# eps_flatsat_module.net
KiCad netlist of a schematic drawn in EAGLE
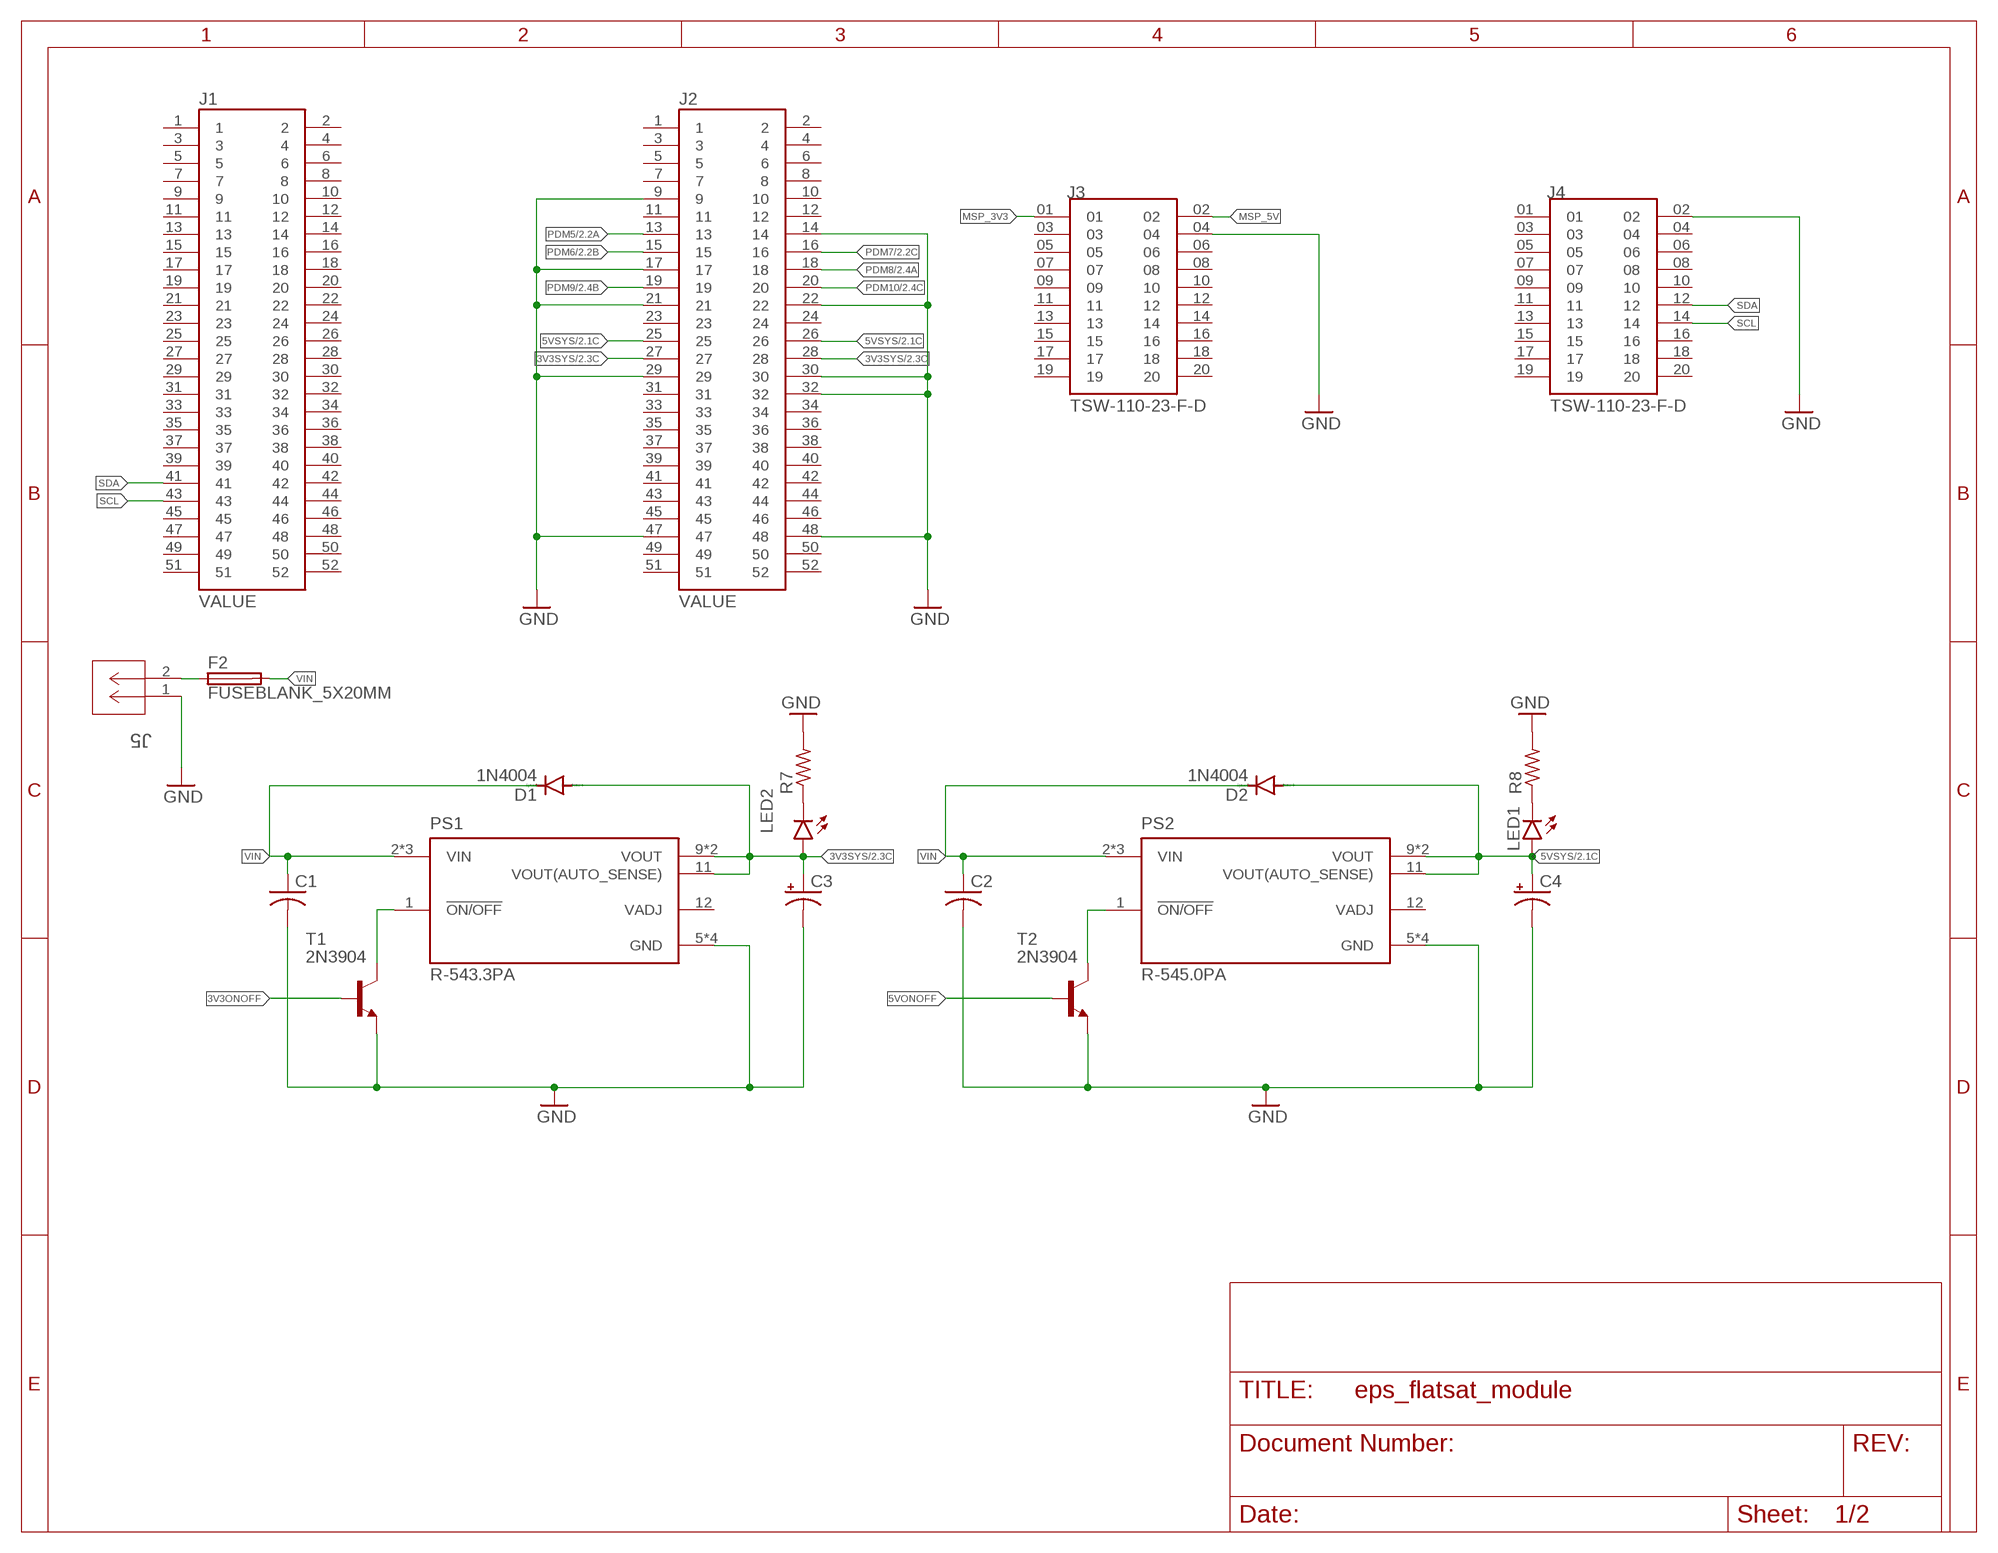
[diagram p0: schematic, sheet 1]
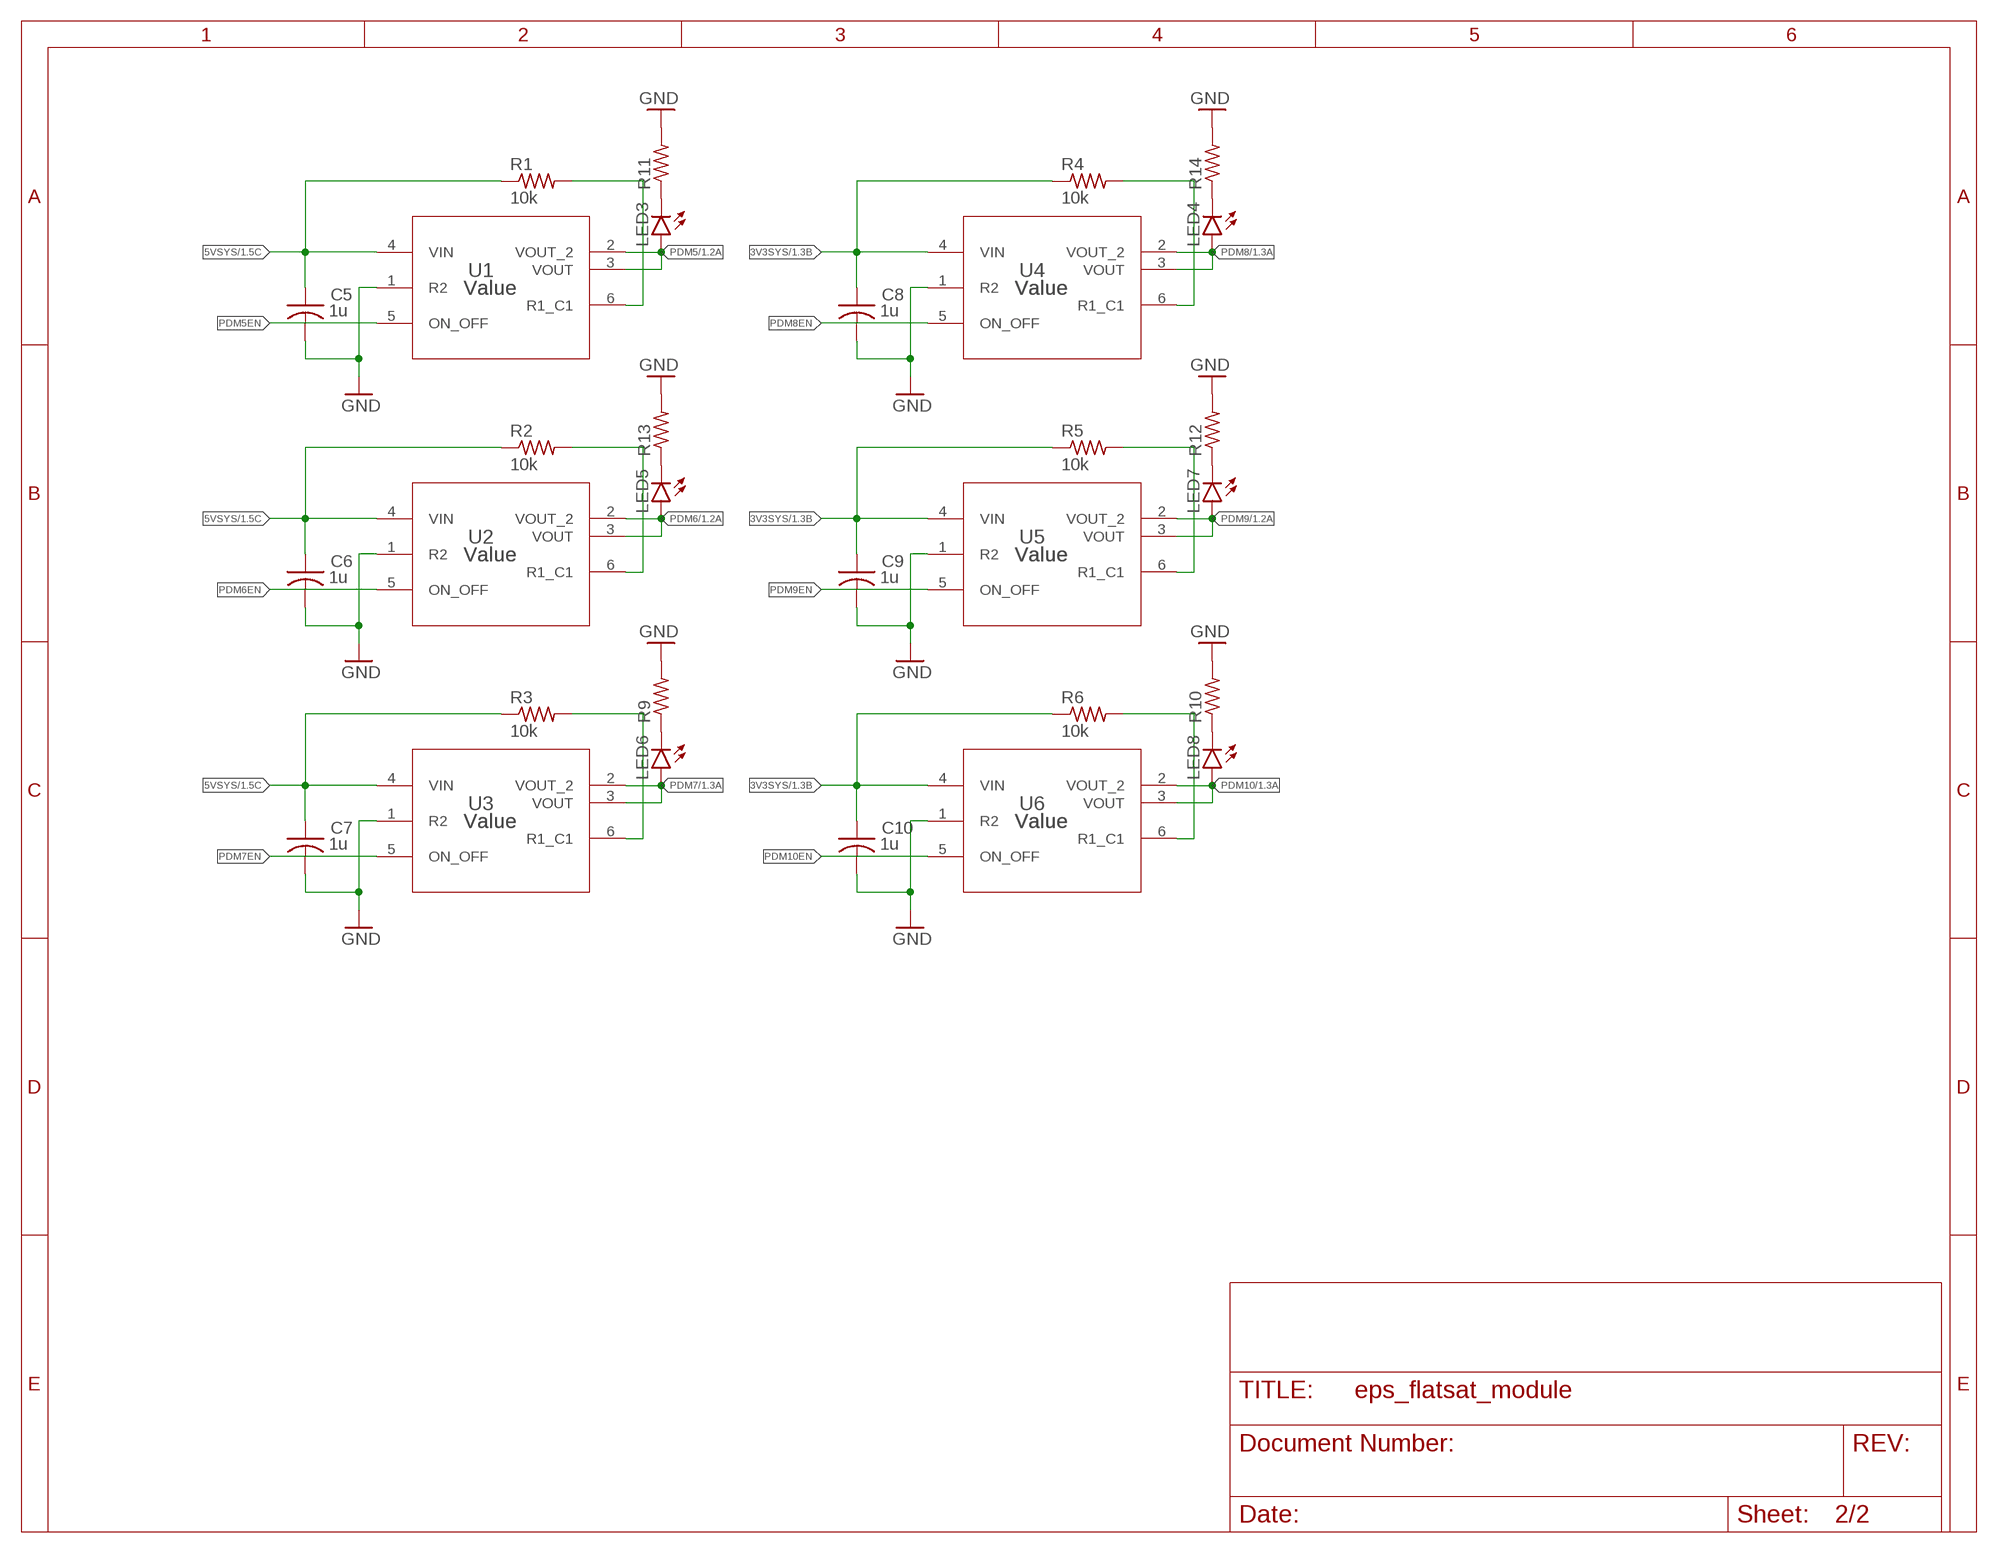
[diagram p1: schematic, sheet 2]

(export (version "E")
  (design (tool "Eeschema 10.0.6"))
  (components
    (comp (ref "C5")
      (value "1u")
      (footprint "eagle-import:C0805")
      (libsource (lib "eagle-import") (part "C-USC0805"))
    )
    (comp (ref "C6")
      (value "1u")
      (footprint "eagle-import:C0805")
      (libsource (lib "eagle-import") (part "C-USC0805"))
    )
    (comp (ref "C7")
      (value "1u")
      (footprint "eagle-import:C0805")
      (libsource (lib "eagle-import") (part "C-USC0805"))
    )
    (comp (ref "C8")
      (value "1u")
      (footprint "eagle-import:C0805")
      (libsource (lib "eagle-import") (part "C-USC0805"))
    )
    (comp (ref "C9")
      (value "1u")
      (footprint "eagle-import:C0805")
      (libsource (lib "eagle-import") (part "C-USC0805"))
    )
    (comp (ref "C10")
      (value "1u")
      (footprint "eagle-import:C0805")
      (libsource (lib "eagle-import") (part "C-USC0805"))
    )
    (comp (ref "LED3")
      (value "LEDCHIPLED_0805")
      (footprint "eagle-import:CHIPLED_0805")
      (libsource (lib "eagle-import") (part "LEDCHIPLED_0805"))
    )
    (comp (ref "LED4")
      (value "LEDCHIPLED_0805")
      (footprint "eagle-import:CHIPLED_0805")
      (libsource (lib "eagle-import") (part "LEDCHIPLED_0805"))
    )
    (comp (ref "LED5")
      (value "LEDCHIPLED_0805")
      (footprint "eagle-import:CHIPLED_0805")
      (libsource (lib "eagle-import") (part "LEDCHIPLED_0805"))
    )
    (comp (ref "LED6")
      (value "LEDCHIPLED_0805")
      (footprint "eagle-import:CHIPLED_0805")
      (libsource (lib "eagle-import") (part "LEDCHIPLED_0805"))
    )
    (comp (ref "LED7")
      (value "LEDCHIPLED_0805")
      (footprint "eagle-import:CHIPLED_0805")
      (libsource (lib "eagle-import") (part "LEDCHIPLED_0805"))
    )
    (comp (ref "LED8")
      (value "LEDCHIPLED_0805")
      (footprint "eagle-import:CHIPLED_0805")
      (libsource (lib "eagle-import") (part "LEDCHIPLED_0805"))
    )
    (comp (ref "R1")
      (value "10k")
      (footprint "eagle-import:R0805")
      (libsource (lib "eagle-import") (part "R-US_R0805"))
    )
    (comp (ref "R2")
      (value "10k")
      (footprint "eagle-import:R0805")
      (libsource (lib "eagle-import") (part "R-US_R0805"))
    )
    (comp (ref "R3")
      (value "10k")
      (footprint "eagle-import:R0805")
      (libsource (lib "eagle-import") (part "R-US_R0805"))
    )
    (comp (ref "R4")
      (value "10k")
      (footprint "eagle-import:R0805")
      (libsource (lib "eagle-import") (part "R-US_R0805"))
    )
    (comp (ref "R5")
      (value "10k")
      (footprint "eagle-import:R0805")
      (libsource (lib "eagle-import") (part "R-US_R0805"))
    )
    (comp (ref "R6")
      (value "10k")
      (footprint "eagle-import:R0805")
      (libsource (lib "eagle-import") (part "R-US_R0805"))
    )
    (comp (ref "R9")
      (value "R-US_R0805")
      (footprint "eagle-import:R0805")
      (libsource (lib "eagle-import") (part "R-US_R0805"))
    )
    (comp (ref "R10")
      (value "R-US_R0805")
      (footprint "eagle-import:R0805")
      (libsource (lib "eagle-import") (part "R-US_R0805"))
    )
    (comp (ref "R11")
      (value "R-US_R0805")
      (footprint "eagle-import:R0805")
      (libsource (lib "eagle-import") (part "R-US_R0805"))
    )
    (comp (ref "R12")
      (value "R-US_R0805")
      (footprint "eagle-import:R0805")
      (libsource (lib "eagle-import") (part "R-US_R0805"))
    )
    (comp (ref "R13")
      (value "R-US_R0805")
      (footprint "eagle-import:R0805")
      (libsource (lib "eagle-import") (part "R-US_R0805"))
    )
    (comp (ref "R14")
      (value "R-US_R0805")
      (footprint "eagle-import:R0805")
      (libsource (lib "eagle-import") (part "R-US_R0805"))
    )
    (comp (ref "U1")
      (value "Value")
      (footprint "eagle-import:DDC0006A_N")
      (fields (field (name "MANUFACTURER") "Texas Instruments") (field (name "PARTNUMBER") "TPS27081ADDCR"))
      (libsource (lib "eagle-import") (part "TPS27081ADDCR"))
    )
    (comp (ref "U2")
      (value "Value")
      (footprint "eagle-import:DDC0006A_N")
      (fields (field (name "MANUFACTURER") "Texas Instruments") (field (name "PARTNUMBER") "TPS27081ADDCR"))
      (libsource (lib "eagle-import") (part "TPS27081ADDCR"))
    )
    (comp (ref "U3")
      (value "Value")
      (footprint "eagle-import:DDC0006A_N")
      (fields (field (name "MANUFACTURER") "Texas Instruments") (field (name "PARTNUMBER") "TPS27081ADDCR"))
      (libsource (lib "eagle-import") (part "TPS27081ADDCR"))
    )
    (comp (ref "U4")
      (value "Value")
      (footprint "eagle-import:DDC0006A_N")
      (fields (field (name "MANUFACTURER") "Texas Instruments") (field (name "PARTNUMBER") "TPS27081ADDCR"))
      (libsource (lib "eagle-import") (part "TPS27081ADDCR"))
    )
    (comp (ref "U5")
      (value "Value")
      (footprint "eagle-import:DDC0006A_N")
      (fields (field (name "MANUFACTURER") "Texas Instruments") (field (name "PARTNUMBER") "TPS27081ADDCR"))
      (libsource (lib "eagle-import") (part "TPS27081ADDCR"))
    )
    (comp (ref "U6")
      (value "Value")
      (footprint "eagle-import:DDC0006A_N")
      (fields (field (name "MANUFACTURER") "Texas Instruments") (field (name "PARTNUMBER") "TPS27081ADDCR"))
      (libsource (lib "eagle-import") (part "TPS27081ADDCR"))
    )
    (comp (ref "C1")
      (value "C-USC0805")
      (footprint "eagle-import:C0805")
      (libsource (lib "eagle-import") (part "C-USC0805"))
    )
    (comp (ref "C2")
      (value "C-USC0805")
      (footprint "eagle-import:C0805")
      (libsource (lib "eagle-import") (part "C-USC0805"))
    )
    (comp (ref "C3")
      (value "CPOL-USE2.5-6")
      (footprint "eagle-import:E2,5-6")
      (libsource (lib "eagle-import") (part "CPOL-USE2.5-6"))
    )
    (comp (ref "C4")
      (value "CPOL-USE2.5-6")
      (footprint "eagle-import:E2,5-6")
      (libsource (lib "eagle-import") (part "CPOL-USE2.5-6"))
    )
    (comp (ref "D1")
      (value "1N4004")
      (footprint "eagle-import:DO41-10")
      (libsource (lib "eagle-import") (part "1N4004"))
    )
    (comp (ref "D2")
      (value "1N4004")
      (footprint "eagle-import:DO41-10")
      (libsource (lib "eagle-import") (part "1N4004"))
    )
    (comp (ref "F2")
      (value "FUSEBLANK_5X20MM")
      (footprint "eagle-import:FUSE_HOLDER_5X20MM")
      (libsource (lib "eagle-import") (part "FUSEBLANK_5X20MM"))
    )
    (comp (ref "J1")
      (value "ESQ-126-39-G-D")
      (footprint "eagle-import:SAMTEC_ESQ-126-39-G-D")
      (fields (field (name "DIGI-KEY_PART_NUMBER") "SAM10462-ND") (field (name "MF") "Samtec"))
      (libsource (lib "eagle-import") (part "ESQ-126-39-G-D"))
    )
    (comp (ref "J2")
      (value "ESQ-126-39-G-D")
      (footprint "eagle-import:SAMTEC_ESQ-126-39-G-D")
      (fields (field (name "DIGI-KEY_PART_NUMBER") "SAM10462-ND") (field (name "MF") "Samtec"))
      (libsource (lib "eagle-import") (part "ESQ-126-39-G-D"))
    )
    (comp (ref "J3")
      (value "TSW-110-23-F-D")
      (footprint "eagle-import:SAMTEC_TSW-110-23-F-D")
      (fields (field (name "MANUFACTURER") "Samtec"))
      (libsource (lib "eagle-import") (part "TSW-110-23-F-D"))
    )
    (comp (ref "J4")
      (value "TSW-110-23-F-D")
      (footprint "eagle-import:SAMTEC_TSW-110-23-F-D")
      (fields (field (name "MANUFACTURER") "Samtec"))
      (libsource (lib "eagle-import") (part "TSW-110-23-F-D"))
    )
    (comp (ref "J5")
      (value "1985881")
      (footprint "eagle-import:CONN_1715022_PXC")
      (fields (field (name "COPYRIGHT") "Copyright (C) 2018 Accelerated Designs. All rights reserved"))
      (libsource (lib "eagle-import") (part "1985881"))
    )
    (comp (ref "LED1")
      (value "LEDCHIPLED_0805")
      (footprint "eagle-import:CHIPLED_0805")
      (libsource (lib "eagle-import") (part "LEDCHIPLED_0805"))
    )
    (comp (ref "LED2")
      (value "LEDCHIPLED_0805")
      (footprint "eagle-import:CHIPLED_0805")
      (libsource (lib "eagle-import") (part "LEDCHIPLED_0805"))
    )
    (comp (ref "PS1")
      (value "R-543.3PA")
      (footprint "eagle-import:CONV_R-543.3PA")
      (fields (field (name "DIGI-KEY_PART_NUMBER") "945-1599-5-ND") (field (name "MF") "Recom Power"))
      (libsource (lib "eagle-import") (part "R-543.3PA"))
    )
    (comp (ref "PS2")
      (value "R-545.0PA")
      (footprint "eagle-import:CONV_R-545.0PA")
      (fields (field (name "DIGI-KEY_PART_NUMBER") "R-545.0PA-ND") (field (name "MF") "Recom Power"))
      (libsource (lib "eagle-import") (part "R-545.0PA"))
    )
    (comp (ref "R7")
      (value "R-US_R0805")
      (footprint "eagle-import:R0805")
      (libsource (lib "eagle-import") (part "R-US_R0805"))
    )
    (comp (ref "R8")
      (value "R-US_R0805")
      (footprint "eagle-import:R0805")
      (libsource (lib "eagle-import") (part "R-US_R0805"))
    )
    (comp (ref "T1")
      (value "2N3904")
      (footprint "eagle-import:TO92")
      (libsource (lib "eagle-import") (part "2N3904"))
    )
    (comp (ref "T2")
      (value "2N3904")
      (footprint "eagle-import:TO92")
      (libsource (lib "eagle-import") (part "2N3904"))
    )
  )
  (nets
    (net (code "1") (name "3V3ONOFF") (class "Default")
      (node (ref "T1") (pin "2") (pinfunction "B_2") (pintype "passive"))
    )
    (net (code "2") (name "3V3SYS") (class "Default")
      (node (ref "C10") (pin "1") (pinfunction "1_1") (pintype "passive"))
      (node (ref "C3") (pin "+") (pinfunction "+_+") (pintype "passive"))
      (node (ref "C8") (pin "1") (pinfunction "1_1") (pintype "passive"))
      (node (ref "C9") (pin "1") (pinfunction "1_1") (pintype "passive"))
      (node (ref "D1") (pin "A") (pinfunction "A_A") (pintype "passive"))
      (node (ref "J2") (pin "27") (pinfunction "27_27") (pintype "passive"))
      (node (ref "J2") (pin "28") (pinfunction "28_28") (pintype "passive"))
      (node (ref "LED2") (pin "A") (pinfunction "A_A") (pintype "passive"))
      (node (ref "PS1") (pin "10") (pinfunction "VOUT_10") (pintype "output"))
      (node (ref "PS1") (pin "11") (pinfunction "VOUT(AUTO_SENSE)_11") (pintype "output"))
      (node (ref "PS1") (pin "9") (pinfunction "VOUT_9") (pintype "output"))
      (node (ref "R4") (pin "1") (pinfunction "1_1") (pintype "passive"))
      (node (ref "R5") (pin "1") (pinfunction "1_1") (pintype "passive"))
      (node (ref "R6") (pin "1") (pinfunction "1_1") (pintype "passive"))
      (node (ref "U4") (pin "4") (pinfunction "VIN_4") (pintype "power_in"))
      (node (ref "U5") (pin "4") (pinfunction "VIN_4") (pintype "power_in"))
      (node (ref "U6") (pin "4") (pinfunction "VIN_4") (pintype "power_in"))
    )
    (net (code "3") (name "5VONOFF") (class "Default")
      (node (ref "T2") (pin "2") (pinfunction "B_2") (pintype "passive"))
    )
    (net (code "4") (name "5VSYS") (class "Default")
      (node (ref "C4") (pin "+") (pinfunction "+_+") (pintype "passive"))
      (node (ref "C5") (pin "1") (pinfunction "1_1") (pintype "passive"))
      (node (ref "C6") (pin "1") (pinfunction "1_1") (pintype "passive"))
      (node (ref "C7") (pin "1") (pinfunction "1_1") (pintype "passive"))
      (node (ref "D2") (pin "A") (pinfunction "A_A") (pintype "passive"))
      (node (ref "J2") (pin "25") (pinfunction "25_25") (pintype "passive"))
      (node (ref "J2") (pin "26") (pinfunction "26_26") (pintype "passive"))
      (node (ref "LED1") (pin "A") (pinfunction "A_A") (pintype "passive"))
      (node (ref "PS2") (pin "10") (pinfunction "VOUT_10") (pintype "output"))
      (node (ref "PS2") (pin "11") (pinfunction "VOUT(AUTO_SENSE)_11") (pintype "output"))
      (node (ref "PS2") (pin "9") (pinfunction "VOUT_9") (pintype "output"))
      (node (ref "R1") (pin "1") (pinfunction "1_1") (pintype "passive"))
      (node (ref "R2") (pin "1") (pinfunction "1_1") (pintype "passive"))
      (node (ref "R3") (pin "1") (pinfunction "1_1") (pintype "passive"))
      (node (ref "U1") (pin "4") (pinfunction "VIN_4") (pintype "power_in"))
      (node (ref "U2") (pin "4") (pinfunction "VIN_4") (pintype "power_in"))
      (node (ref "U3") (pin "4") (pinfunction "VIN_4") (pintype "power_in"))
    )
    (net (code "5") (name "GND") (class "Default")
      (node (ref "C1") (pin "2") (pinfunction "2_2") (pintype "passive"))
      (node (ref "C10") (pin "2") (pinfunction "2_2") (pintype "passive"))
      (node (ref "C2") (pin "2") (pinfunction "2_2") (pintype "passive"))
      (node (ref "C3") (pin "-") (pinfunction "-_-") (pintype "passive"))
      (node (ref "C4") (pin "-") (pinfunction "-_-") (pintype "passive"))
      (node (ref "C5") (pin "2") (pinfunction "2_2") (pintype "passive"))
      (node (ref "C6") (pin "2") (pinfunction "2_2") (pintype "passive"))
      (node (ref "C7") (pin "2") (pinfunction "2_2") (pintype "passive"))
      (node (ref "C8") (pin "2") (pinfunction "2_2") (pintype "passive"))
      (node (ref "C9") (pin "2") (pinfunction "2_2") (pintype "passive"))
      (node (ref "J2") (pin "14") (pinfunction "14_14") (pintype "passive"))
      (node (ref "J2") (pin "17") (pinfunction "17_17") (pintype "passive"))
      (node (ref "J2") (pin "21") (pinfunction "21_21") (pintype "passive"))
      (node (ref "J2") (pin "22") (pinfunction "22_22") (pintype "passive"))
      (node (ref "J2") (pin "29") (pinfunction "29_29") (pintype "passive"))
      (node (ref "J2") (pin "30") (pinfunction "30_30") (pintype "passive"))
      (node (ref "J2") (pin "32") (pinfunction "32_32") (pintype "passive"))
      (node (ref "J2") (pin "47") (pinfunction "47_47") (pintype "passive"))
      (node (ref "J2") (pin "48") (pinfunction "48_48") (pintype "passive"))
      (node (ref "J2") (pin "9") (pinfunction "9_9") (pintype "passive"))
      (node (ref "J3") (pin "04") (pinfunction "04_04") (pintype "passive"))
      (node (ref "J4") (pin "02") (pinfunction "02_02") (pintype "passive"))
      (node (ref "J5") (pin "1") (pinfunction "1_1") (pintype "passive"))
      (node (ref "PS1") (pin "5") (pinfunction "GND_5") (pintype "power_in"))
      (node (ref "PS1") (pin "6") (pinfunction "GND_6") (pintype "power_in"))
      (node (ref "PS1") (pin "7") (pinfunction "GND_7") (pintype "power_in"))
      (node (ref "PS1") (pin "8") (pinfunction "GND_8") (pintype "power_in"))
      (node (ref "PS2") (pin "5") (pinfunction "GND_5") (pintype "power_in"))
      (node (ref "PS2") (pin "6") (pinfunction "GND_6") (pintype "power_in"))
      (node (ref "PS2") (pin "7") (pinfunction "GND_7") (pintype "power_in"))
      (node (ref "PS2") (pin "8") (pinfunction "GND_8") (pintype "power_in"))
      (node (ref "R10") (pin "2") (pinfunction "2_2") (pintype "passive"))
      (node (ref "R11") (pin "2") (pinfunction "2_2") (pintype "passive"))
      (node (ref "R12") (pin "2") (pinfunction "2_2") (pintype "passive"))
      (node (ref "R13") (pin "2") (pinfunction "2_2") (pintype "passive"))
      (node (ref "R14") (pin "2") (pinfunction "2_2") (pintype "passive"))
      (node (ref "R7") (pin "2") (pinfunction "2_2") (pintype "passive"))
      (node (ref "R8") (pin "2") (pinfunction "2_2") (pintype "passive"))
      (node (ref "R9") (pin "2") (pinfunction "2_2") (pintype "passive"))
      (node (ref "T1") (pin "3") (pinfunction "E_3") (pintype "passive"))
      (node (ref "T2") (pin "3") (pinfunction "E_3") (pintype "passive"))
      (node (ref "U1") (pin "1") (pinfunction "R2_1") (pintype "input"))
      (node (ref "U2") (pin "1") (pinfunction "R2_1") (pintype "input"))
      (node (ref "U3") (pin "1") (pinfunction "R2_1") (pintype "input"))
      (node (ref "U4") (pin "1") (pinfunction "R2_1") (pintype "input"))
      (node (ref "U5") (pin "1") (pinfunction "R2_1") (pintype "input"))
      (node (ref "U6") (pin "1") (pinfunction "R2_1") (pintype "input"))
    )
    (net (code "6") (name "MSP_3V3") (class "Default")
      (node (ref "J3") (pin "01") (pinfunction "01_01") (pintype "passive"))
    )
    (net (code "7") (name "MSP_5V") (class "Default")
      (node (ref "J3") (pin "02") (pinfunction "02_02") (pintype "passive"))
    )
    (net (code "8") (name "Net-(F2-Pad1)") (class "Default")
      (node (ref "F2") (pin "1") (pinfunction "1_1") (pintype "passive"))
      (node (ref "J5") (pin "2") (pinfunction "2_2") (pintype "passive"))
    )
    (net (code "9") (name "Net-(LED1-PadC)") (class "Default")
      (node (ref "LED1") (pin "C") (pinfunction "C_C") (pintype "passive"))
      (node (ref "R8") (pin "1") (pinfunction "1_1") (pintype "passive"))
    )
    (net (code "10") (name "Net-(LED2-PadC)") (class "Default")
      (node (ref "LED2") (pin "C") (pinfunction "C_C") (pintype "passive"))
      (node (ref "R7") (pin "1") (pinfunction "1_1") (pintype "passive"))
    )
    (net (code "11") (name "Net-(LED3-PadC)") (class "Default")
      (node (ref "LED3") (pin "C") (pinfunction "C_C") (pintype "passive"))
      (node (ref "R11") (pin "1") (pinfunction "1_1") (pintype "passive"))
    )
    (net (code "12") (name "Net-(LED4-PadC)") (class "Default")
      (node (ref "LED4") (pin "C") (pinfunction "C_C") (pintype "passive"))
      (node (ref "R14") (pin "1") (pinfunction "1_1") (pintype "passive"))
    )
    (net (code "13") (name "Net-(LED5-PadC)") (class "Default")
      (node (ref "LED5") (pin "C") (pinfunction "C_C") (pintype "passive"))
      (node (ref "R13") (pin "1") (pinfunction "1_1") (pintype "passive"))
    )
    (net (code "14") (name "Net-(LED6-PadC)") (class "Default")
      (node (ref "LED6") (pin "C") (pinfunction "C_C") (pintype "passive"))
      (node (ref "R9") (pin "1") (pinfunction "1_1") (pintype "passive"))
    )
    (net (code "15") (name "Net-(LED7-PadC)") (class "Default")
      (node (ref "LED7") (pin "C") (pinfunction "C_C") (pintype "passive"))
      (node (ref "R12") (pin "1") (pinfunction "1_1") (pintype "passive"))
    )
    (net (code "16") (name "Net-(LED8-PadC)") (class "Default")
      (node (ref "LED8") (pin "C") (pinfunction "C_C") (pintype "passive"))
      (node (ref "R10") (pin "1") (pinfunction "1_1") (pintype "passive"))
    )
    (net (code "17") (name "Net-(PS1-~{ON{slash}OFF})") (class "Default")
      (node (ref "PS1") (pin "1") (pinfunction "~{ON/OFF}_1") (pintype "input"))
      (node (ref "T1") (pin "1") (pinfunction "C_1") (pintype "passive"))
    )
    (net (code "18") (name "Net-(PS2-~{ON{slash}OFF})") (class "Default")
      (node (ref "PS2") (pin "1") (pinfunction "~{ON/OFF}_1") (pintype "input"))
      (node (ref "T2") (pin "1") (pinfunction "C_1") (pintype "passive"))
    )
    (net (code "19") (name "Net-(U1-R1_C1)") (class "Default")
      (node (ref "R1") (pin "2") (pinfunction "2_2") (pintype "passive"))
      (node (ref "U1") (pin "6") (pinfunction "R1_C1_6") (pintype "input"))
    )
    (net (code "20") (name "Net-(U2-R1_C1)") (class "Default")
      (node (ref "R2") (pin "2") (pinfunction "2_2") (pintype "passive"))
      (node (ref "U2") (pin "6") (pinfunction "R1_C1_6") (pintype "input"))
    )
    (net (code "21") (name "Net-(U3-R1_C1)") (class "Default")
      (node (ref "R3") (pin "2") (pinfunction "2_2") (pintype "passive"))
      (node (ref "U3") (pin "6") (pinfunction "R1_C1_6") (pintype "input"))
    )
    (net (code "22") (name "Net-(U4-R1_C1)") (class "Default")
      (node (ref "R4") (pin "2") (pinfunction "2_2") (pintype "passive"))
      (node (ref "U4") (pin "6") (pinfunction "R1_C1_6") (pintype "input"))
    )
    (net (code "23") (name "Net-(U5-R1_C1)") (class "Default")
      (node (ref "R5") (pin "2") (pinfunction "2_2") (pintype "passive"))
      (node (ref "U5") (pin "6") (pinfunction "R1_C1_6") (pintype "input"))
    )
    (net (code "24") (name "Net-(U6-R1_C1)") (class "Default")
      (node (ref "R6") (pin "2") (pinfunction "2_2") (pintype "passive"))
      (node (ref "U6") (pin "6") (pinfunction "R1_C1_6") (pintype "input"))
    )
    (net (code "25") (name "PDM5") (class "Default")
      (node (ref "J2") (pin "13") (pinfunction "13_13") (pintype "passive"))
      (node (ref "LED3") (pin "A") (pinfunction "A_A") (pintype "passive"))
      (node (ref "U1") (pin "2") (pinfunction "VOUT_2_2") (pintype "power_in"))
      (node (ref "U1") (pin "3") (pinfunction "VOUT_3") (pintype "power_in"))
    )
    (net (code "26") (name "PDM5EN") (class "Default")
      (node (ref "U1") (pin "5") (pinfunction "ON_OFF_5") (pintype "input"))
    )
    (net (code "27") (name "PDM6") (class "Default")
      (node (ref "J2") (pin "15") (pinfunction "15_15") (pintype "passive"))
      (node (ref "LED5") (pin "A") (pinfunction "A_A") (pintype "passive"))
      (node (ref "U2") (pin "2") (pinfunction "VOUT_2_2") (pintype "power_in"))
      (node (ref "U2") (pin "3") (pinfunction "VOUT_3") (pintype "power_in"))
    )
    (net (code "28") (name "PDM6EN") (class "Default")
      (node (ref "U2") (pin "5") (pinfunction "ON_OFF_5") (pintype "input"))
    )
    (net (code "29") (name "PDM7") (class "Default")
      (node (ref "J2") (pin "16") (pinfunction "16_16") (pintype "passive"))
      (node (ref "LED6") (pin "A") (pinfunction "A_A") (pintype "passive"))
      (node (ref "U3") (pin "2") (pinfunction "VOUT_2_2") (pintype "power_in"))
      (node (ref "U3") (pin "3") (pinfunction "VOUT_3") (pintype "power_in"))
    )
    (net (code "30") (name "PDM7EN") (class "Default")
      (node (ref "U3") (pin "5") (pinfunction "ON_OFF_5") (pintype "input"))
    )
    (net (code "31") (name "PDM8") (class "Default")
      (node (ref "J2") (pin "18") (pinfunction "18_18") (pintype "passive"))
      (node (ref "LED4") (pin "A") (pinfunction "A_A") (pintype "passive"))
      (node (ref "U4") (pin "2") (pinfunction "VOUT_2_2") (pintype "power_in"))
      (node (ref "U4") (pin "3") (pinfunction "VOUT_3") (pintype "power_in"))
    )
    (net (code "32") (name "PDM8EN") (class "Default")
      (node (ref "U4") (pin "5") (pinfunction "ON_OFF_5") (pintype "input"))
    )
    (net (code "33") (name "PDM9") (class "Default")
      (node (ref "J2") (pin "19") (pinfunction "19_19") (pintype "passive"))
      (node (ref "LED7") (pin "A") (pinfunction "A_A") (pintype "passive"))
      (node (ref "U5") (pin "2") (pinfunction "VOUT_2_2") (pintype "power_in"))
      (node (ref "U5") (pin "3") (pinfunction "VOUT_3") (pintype "power_in"))
    )
    (net (code "34") (name "PDM9EN") (class "Default")
      (node (ref "U5") (pin "5") (pinfunction "ON_OFF_5") (pintype "input"))
    )
    (net (code "35") (name "PDM10") (class "Default")
      (node (ref "J2") (pin "20") (pinfunction "20_20") (pintype "passive"))
      (node (ref "LED8") (pin "A") (pinfunction "A_A") (pintype "passive"))
      (node (ref "U6") (pin "2") (pinfunction "VOUT_2_2") (pintype "power_in"))
      (node (ref "U6") (pin "3") (pinfunction "VOUT_3") (pintype "power_in"))
    )
    (net (code "36") (name "PDM10EN") (class "Default")
      (node (ref "U6") (pin "5") (pinfunction "ON_OFF_5") (pintype "input"))
    )
    (net (code "37") (name "SCL") (class "Default")
      (node (ref "J1") (pin "43") (pinfunction "43_43") (pintype "passive"))
      (node (ref "J4") (pin "14") (pinfunction "14_14") (pintype "passive"))
    )
    (net (code "38") (name "SDA") (class "Default")
      (node (ref "J1") (pin "41") (pinfunction "41_41") (pintype "passive"))
      (node (ref "J4") (pin "12") (pinfunction "12_12") (pintype "passive"))
    )
    (net (code "39") (name "VIN") (class "Default")
      (node (ref "C1") (pin "1") (pinfunction "1_1") (pintype "passive"))
      (node (ref "C2") (pin "1") (pinfunction "1_1") (pintype "passive"))
      (node (ref "D1") (pin "C") (pinfunction "C_C") (pintype "passive"))
      (node (ref "D2") (pin "C") (pinfunction "C_C") (pintype "passive"))
      (node (ref "F2") (pin "2") (pinfunction "2_2") (pintype "passive"))
      (node (ref "PS1") (pin "2") (pinfunction "VIN_2") (pintype "input"))
      (node (ref "PS1") (pin "3") (pinfunction "VIN_3") (pintype "input"))
      (node (ref "PS1") (pin "4") (pinfunction "VIN_4") (pintype "input"))
      (node (ref "PS2") (pin "2") (pinfunction "VIN_2") (pintype "input"))
      (node (ref "PS2") (pin "3") (pinfunction "VIN_3") (pintype "input"))
      (node (ref "PS2") (pin "4") (pinfunction "VIN_4") (pintype "input"))
    )
    (net (code "40") (name "unconnected-(J1-Pad1)") (class "Default")
      (node (ref "J1") (pin "1") (pinfunction "1_1") (pintype "passive"))
    )
    (net (code "41") (name "unconnected-(J1-Pad2)") (class "Default")
      (node (ref "J1") (pin "2") (pinfunction "2_2") (pintype "passive"))
    )
    (net (code "42") (name "unconnected-(J1-Pad3)") (class "Default")
      (node (ref "J1") (pin "3") (pinfunction "3_3") (pintype "passive"))
    )
    (net (code "43") (name "unconnected-(J1-Pad4)") (class "Default")
      (node (ref "J1") (pin "4") (pinfunction "4_4") (pintype "passive"))
    )
    (net (code "44") (name "unconnected-(J1-Pad5)") (class "Default")
      (node (ref "J1") (pin "5") (pinfunction "5_5") (pintype "passive"))
    )
    (net (code "45") (name "unconnected-(J1-Pad6)") (class "Default")
      (node (ref "J1") (pin "6") (pinfunction "6_6") (pintype "passive"))
    )
    (net (code "46") (name "unconnected-(J1-Pad7)") (class "Default")
      (node (ref "J1") (pin "7") (pinfunction "7_7") (pintype "passive"))
    )
    (net (code "47") (name "unconnected-(J1-Pad8)") (class "Default")
      (node (ref "J1") (pin "8") (pinfunction "8_8") (pintype "passive"))
    )
    (net (code "48") (name "unconnected-(J1-Pad9)") (class "Default")
      (node (ref "J1") (pin "9") (pinfunction "9_9") (pintype "passive"))
    )
    (net (code "49") (name "unconnected-(J1-Pad10)") (class "Default")
      (node (ref "J1") (pin "10") (pinfunction "10_10") (pintype "passive"))
    )
    (net (code "50") (name "unconnected-(J1-Pad11)") (class "Default")
      (node (ref "J1") (pin "11") (pinfunction "11_11") (pintype "passive"))
    )
    (net (code "51") (name "unconnected-(J1-Pad12)") (class "Default")
      (node (ref "J1") (pin "12") (pinfunction "12_12") (pintype "passive"))
    )
    (net (code "52") (name "unconnected-(J1-Pad13)") (class "Default")
      (node (ref "J1") (pin "13") (pinfunction "13_13") (pintype "passive"))
    )
    (net (code "53") (name "unconnected-(J1-Pad14)") (class "Default")
      (node (ref "J1") (pin "14") (pinfunction "14_14") (pintype "passive"))
    )
    (net (code "54") (name "unconnected-(J1-Pad15)") (class "Default")
      (node (ref "J1") (pin "15") (pinfunction "15_15") (pintype "passive"))
    )
    (net (code "55") (name "unconnected-(J1-Pad16)") (class "Default")
      (node (ref "J1") (pin "16") (pinfunction "16_16") (pintype "passive"))
    )
    (net (code "56") (name "unconnected-(J1-Pad17)") (class "Default")
      (node (ref "J1") (pin "17") (pinfunction "17_17") (pintype "passive"))
    )
    (net (code "57") (name "unconnected-(J1-Pad18)") (class "Default")
      (node (ref "J1") (pin "18") (pinfunction "18_18") (pintype "passive"))
    )
    (net (code "58") (name "unconnected-(J1-Pad19)") (class "Default")
      (node (ref "J1") (pin "19") (pinfunction "19_19") (pintype "passive"))
    )
    (net (code "59") (name "unconnected-(J1-Pad20)") (class "Default")
      (node (ref "J1") (pin "20") (pinfunction "20_20") (pintype "passive"))
    )
    (net (code "60") (name "unconnected-(J1-Pad21)") (class "Default")
      (node (ref "J1") (pin "21") (pinfunction "21_21") (pintype "passive"))
    )
    (net (code "61") (name "unconnected-(J1-Pad22)") (class "Default")
      (node (ref "J1") (pin "22") (pinfunction "22_22") (pintype "passive"))
    )
    (net (code "62") (name "unconnected-(J1-Pad23)") (class "Default")
      (node (ref "J1") (pin "23") (pinfunction "23_23") (pintype "passive"))
    )
    (net (code "63") (name "unconnected-(J1-Pad24)") (class "Default")
      (node (ref "J1") (pin "24") (pinfunction "24_24") (pintype "passive"))
    )
    (net (code "64") (name "unconnected-(J1-Pad25)") (class "Default")
      (node (ref "J1") (pin "25") (pinfunction "25_25") (pintype "passive"))
    )
    (net (code "65") (name "unconnected-(J1-Pad26)") (class "Default")
      (node (ref "J1") (pin "26") (pinfunction "26_26") (pintype "passive"))
    )
    (net (code "66") (name "unconnected-(J1-Pad27)") (class "Default")
      (node (ref "J1") (pin "27") (pinfunction "27_27") (pintype "passive"))
    )
    (net (code "67") (name "unconnected-(J1-Pad28)") (class "Default")
      (node (ref "J1") (pin "28") (pinfunction "28_28") (pintype "passive"))
    )
    (net (code "68") (name "unconnected-(J1-Pad29)") (class "Default")
      (node (ref "J1") (pin "29") (pinfunction "29_29") (pintype "passive"))
    )
    (net (code "69") (name "unconnected-(J1-Pad30)") (class "Default")
      (node (ref "J1") (pin "30") (pinfunction "30_30") (pintype "passive"))
    )
    (net (code "70") (name "unconnected-(J1-Pad31)") (class "Default")
      (node (ref "J1") (pin "31") (pinfunction "31_31") (pintype "passive"))
    )
    (net (code "71") (name "unconnected-(J1-Pad32)") (class "Default")
      (node (ref "J1") (pin "32") (pinfunction "32_32") (pintype "passive"))
    )
    (net (code "72") (name "unconnected-(J1-Pad33)") (class "Default")
      (node (ref "J1") (pin "33") (pinfunction "33_33") (pintype "passive"))
    )
    (net (code "73") (name "unconnected-(J1-Pad34)") (class "Default")
      (node (ref "J1") (pin "34") (pinfunction "34_34") (pintype "passive"))
    )
    (net (code "74") (name "unconnected-(J1-Pad35)") (class "Default")
      (node (ref "J1") (pin "35") (pinfunction "35_35") (pintype "passive"))
    )
    (net (code "75") (name "unconnected-(J1-Pad36)") (class "Default")
      (node (ref "J1") (pin "36") (pinfunction "36_36") (pintype "passive"))
    )
    (net (code "76") (name "unconnected-(J1-Pad37)") (class "Default")
      (node (ref "J1") (pin "37") (pinfunction "37_37") (pintype "passive"))
    )
    (net (code "77") (name "unconnected-(J1-Pad38)") (class "Default")
      (node (ref "J1") (pin "38") (pinfunction "38_38") (pintype "passive"))
    )
    (net (code "78") (name "unconnected-(J1-Pad39)") (class "Default")
      (node (ref "J1") (pin "39") (pinfunction "39_39") (pintype "passive"))
    )
    (net (code "79") (name "unconnected-(J1-Pad40)") (class "Default")
      (node (ref "J1") (pin "40") (pinfunction "40_40") (pintype "passive"))
    )
    (net (code "80") (name "unconnected-(J1-Pad42)") (class "Default")
      (node (ref "J1") (pin "42") (pinfunction "42_42") (pintype "passive"))
    )
    (net (code "81") (name "unconnected-(J1-Pad44)") (class "Default")
      (node (ref "J1") (pin "44") (pinfunction "44_44") (pintype "passive"))
    )
    (net (code "82") (name "unconnected-(J1-Pad45)") (class "Default")
      (node (ref "J1") (pin "45") (pinfunction "45_45") (pintype "passive"))
    )
    (net (code "83") (name "unconnected-(J1-Pad46)") (class "Default")
      (node (ref "J1") (pin "46") (pinfunction "46_46") (pintype "passive"))
    )
    (net (code "84") (name "unconnected-(J1-Pad47)") (class "Default")
      (node (ref "J1") (pin "47") (pinfunction "47_47") (pintype "passive"))
    )
    (net (code "85") (name "unconnected-(J1-Pad48)") (class "Default")
      (node (ref "J1") (pin "48") (pinfunction "48_48") (pintype "passive"))
    )
    (net (code "86") (name "unconnected-(J1-Pad49)") (class "Default")
      (node (ref "J1") (pin "49") (pinfunction "49_49") (pintype "passive"))
    )
    (net (code "87") (name "unconnected-(J1-Pad50)") (class "Default")
      (node (ref "J1") (pin "50") (pinfunction "50_50") (pintype "passive"))
    )
    (net (code "88") (name "unconnected-(J1-Pad51)") (class "Default")
      (node (ref "J1") (pin "51") (pinfunction "51_51") (pintype "passive"))
    )
    (net (code "89") (name "unconnected-(J1-Pad52)") (class "Default")
      (node (ref "J1") (pin "52") (pinfunction "52_52") (pintype "passive"))
    )
    (net (code "90") (name "unconnected-(J2-Pad1)") (class "Default")
      (node (ref "J2") (pin "1") (pinfunction "1_1") (pintype "passive"))
    )
    (net (code "91") (name "unconnected-(J2-Pad2)") (class "Default")
      (node (ref "J2") (pin "2") (pinfunction "2_2") (pintype "passive"))
    )
    (net (code "92") (name "unconnected-(J2-Pad3)") (class "Default")
      (node (ref "J2") (pin "3") (pinfunction "3_3") (pintype "passive"))
    )
    (net (code "93") (name "unconnected-(J2-Pad4)") (class "Default")
      (node (ref "J2") (pin "4") (pinfunction "4_4") (pintype "passive"))
    )
    (net (code "94") (name "unconnected-(J2-Pad5)") (class "Default")
      (node (ref "J2") (pin "5") (pinfunction "5_5") (pintype "passive"))
    )
    (net (code "95") (name "unconnected-(J2-Pad6)") (class "Default")
      (node (ref "J2") (pin "6") (pinfunction "6_6") (pintype "passive"))
    )
    (net (code "96") (name "unconnected-(J2-Pad7)") (class "Default")
      (node (ref "J2") (pin "7") (pinfunction "7_7") (pintype "passive"))
    )
    (net (code "97") (name "unconnected-(J2-Pad8)") (class "Default")
      (node (ref "J2") (pin "8") (pinfunction "8_8") (pintype "passive"))
    )
    (net (code "98") (name "unconnected-(J2-Pad10)") (class "Default")
      (node (ref "J2") (pin "10") (pinfunction "10_10") (pintype "passive"))
    )
    (net (code "99") (name "unconnected-(J2-Pad11)") (class "Default")
      (node (ref "J2") (pin "11") (pinfunction "11_11") (pintype "passive"))
    )
    (net (code "100") (name "unconnected-(J2-Pad12)") (class "Default")
      (node (ref "J2") (pin "12") (pinfunction "12_12") (pintype "passive"))
    )
    (net (code "101") (name "unconnected-(J2-Pad23)") (class "Default")
      (node (ref "J2") (pin "23") (pinfunction "23_23") (pintype "passive"))
    )
    (net (code "102") (name "unconnected-(J2-Pad24)") (class "Default")
      (node (ref "J2") (pin "24") (pinfunction "24_24") (pintype "passive"))
    )
    (net (code "103") (name "unconnected-(J2-Pad31)") (class "Default")
      (node (ref "J2") (pin "31") (pinfunction "31_31") (pintype "passive"))
    )
    (net (code "104") (name "unconnected-(J2-Pad33)") (class "Default")
      (node (ref "J2") (pin "33") (pinfunction "33_33") (pintype "passive"))
    )
    (net (code "105") (name "unconnected-(J2-Pad34)") (class "Default")
      (node (ref "J2") (pin "34") (pinfunction "34_34") (pintype "passive"))
    )
    (net (code "106") (name "unconnected-(J2-Pad35)") (class "Default")
      (node (ref "J2") (pin "35") (pinfunction "35_35") (pintype "passive"))
    )
    (net (code "107") (name "unconnected-(J2-Pad36)") (class "Default")
      (node (ref "J2") (pin "36") (pinfunction "36_36") (pintype "passive"))
    )
    (net (code "108") (name "unconnected-(J2-Pad37)") (class "Default")
      (node (ref "J2") (pin "37") (pinfunction "37_37") (pintype "passive"))
    )
    (net (code "109") (name "unconnected-(J2-Pad38)") (class "Default")
      (node (ref "J2") (pin "38") (pinfunction "38_38") (pintype "passive"))
    )
    (net (code "110") (name "unconnected-(J2-Pad39)") (class "Default")
      (node (ref "J2") (pin "39") (pinfunction "39_39") (pintype "passive"))
    )
    (net (code "111") (name "unconnected-(J2-Pad40)") (class "Default")
      (node (ref "J2") (pin "40") (pinfunction "40_40") (pintype "passive"))
    )
    (net (code "112") (name "unconnected-(J2-Pad41)") (class "Default")
      (node (ref "J2") (pin "41") (pinfunction "41_41") (pintype "passive"))
    )
    (net (code "113") (name "unconnected-(J2-Pad42)") (class "Default")
      (node (ref "J2") (pin "42") (pinfunction "42_42") (pintype "passive"))
    )
    (net (code "114") (name "unconnected-(J2-Pad43)") (class "Default")
      (node (ref "J2") (pin "43") (pinfunction "43_43") (pintype "passive"))
    )
    (net (code "115") (name "unconnected-(J2-Pad44)") (class "Default")
      (node (ref "J2") (pin "44") (pinfunction "44_44") (pintype "passive"))
    )
    (net (code "116") (name "unconnected-(J2-Pad45)") (class "Default")
      (node (ref "J2") (pin "45") (pinfunction "45_45") (pintype "passive"))
    )
    (net (code "117") (name "unconnected-(J2-Pad46)") (class "Default")
      (node (ref "J2") (pin "46") (pinfunction "46_46") (pintype "passive"))
    )
    (net (code "118") (name "unconnected-(J2-Pad49)") (class "Default")
      (node (ref "J2") (pin "49") (pinfunction "49_49") (pintype "passive"))
    )
    (net (code "119") (name "unconnected-(J2-Pad50)") (class "Default")
      (node (ref "J2") (pin "50") (pinfunction "50_50") (pintype "passive"))
    )
    (net (code "120") (name "unconnected-(J2-Pad51)") (class "Default")
      (node (ref "J2") (pin "51") (pinfunction "51_51") (pintype "passive"))
    )
    (net (code "121") (name "unconnected-(J2-Pad52)") (class "Default")
      (node (ref "J2") (pin "52") (pinfunction "52_52") (pintype "passive"))
    )
    (net (code "122") (name "unconnected-(J3-Pad03)") (class "Default")
      (node (ref "J3") (pin "03") (pinfunction "03_03") (pintype "passive"))
    )
    (net (code "123") (name "unconnected-(J3-Pad05)") (class "Default")
      (node (ref "J3") (pin "05") (pinfunction "05_05") (pintype "passive"))
    )
    (net (code "124") (name "unconnected-(J3-Pad06)") (class "Default")
      (node (ref "J3") (pin "06") (pinfunction "06_06") (pintype "passive"))
    )
    (net (code "125") (name "unconnected-(J3-Pad07)") (class "Default")
      (node (ref "J3") (pin "07") (pinfunction "07_07") (pintype "passive"))
    )
    (net (code "126") (name "unconnected-(J3-Pad08)") (class "Default")
      (node (ref "J3") (pin "08") (pinfunction "08_08") (pintype "passive"))
    )
    (net (code "127") (name "unconnected-(J3-Pad09)") (class "Default")
      (node (ref "J3") (pin "09") (pinfunction "09_09") (pintype "passive"))
    )
    (net (code "128") (name "unconnected-(J3-Pad10)") (class "Default")
      (node (ref "J3") (pin "10") (pinfunction "10_10") (pintype "passive"))
    )
    (net (code "129") (name "unconnected-(J3-Pad11)") (class "Default")
      (node (ref "J3") (pin "11") (pinfunction "11_11") (pintype "passive"))
    )
    (net (code "130") (name "unconnected-(J3-Pad12)") (class "Default")
      (node (ref "J3") (pin "12") (pinfunction "12_12") (pintype "passive"))
    )
    (net (code "131") (name "unconnected-(J3-Pad13)") (class "Default")
      (node (ref "J3") (pin "13") (pinfunction "13_13") (pintype "passive"))
    )
    (net (code "132") (name "unconnected-(J3-Pad14)") (class "Default")
      (node (ref "J3") (pin "14") (pinfunction "14_14") (pintype "passive"))
    )
    (net (code "133") (name "unconnected-(J3-Pad15)") (class "Default")
      (node (ref "J3") (pin "15") (pinfunction "15_15") (pintype "passive"))
    )
    (net (code "134") (name "unconnected-(J3-Pad16)") (class "Default")
      (node (ref "J3") (pin "16") (pinfunction "16_16") (pintype "passive"))
    )
    (net (code "135") (name "unconnected-(J3-Pad17)") (class "Default")
      (node (ref "J3") (pin "17") (pinfunction "17_17") (pintype "passive"))
    )
    (net (code "136") (name "unconnected-(J3-Pad18)") (class "Default")
      (node (ref "J3") (pin "18") (pinfunction "18_18") (pintype "passive"))
    )
    (net (code "137") (name "unconnected-(J3-Pad19)") (class "Default")
      (node (ref "J3") (pin "19") (pinfunction "19_19") (pintype "passive"))
    )
    (net (code "138") (name "unconnected-(J3-Pad20)") (class "Default")
      (node (ref "J3") (pin "20") (pinfunction "20_20") (pintype "passive"))
    )
    (net (code "139") (name "unconnected-(J4-Pad01)") (class "Default")
      (node (ref "J4") (pin "01") (pinfunction "01_01") (pintype "passive"))
    )
    (net (code "140") (name "unconnected-(J4-Pad03)") (class "Default")
      (node (ref "J4") (pin "03") (pinfunction "03_03") (pintype "passive"))
    )
    (net (code "141") (name "unconnected-(J4-Pad04)") (class "Default")
      (node (ref "J4") (pin "04") (pinfunction "04_04") (pintype "passive"))
    )
    (net (code "142") (name "unconnected-(J4-Pad05)") (class "Default")
      (node (ref "J4") (pin "05") (pinfunction "05_05") (pintype "passive"))
    )
    (net (code "143") (name "unconnected-(J4-Pad06)") (class "Default")
      (node (ref "J4") (pin "06") (pinfunction "06_06") (pintype "passive"))
    )
    (net (code "144") (name "unconnected-(J4-Pad07)") (class "Default")
      (node (ref "J4") (pin "07") (pinfunction "07_07") (pintype "passive"))
    )
    (net (code "145") (name "unconnected-(J4-Pad08)") (class "Default")
      (node (ref "J4") (pin "08") (pinfunction "08_08") (pintype "passive"))
    )
    (net (code "146") (name "unconnected-(J4-Pad09)") (class "Default")
      (node (ref "J4") (pin "09") (pinfunction "09_09") (pintype "passive"))
    )
    (net (code "147") (name "unconnected-(J4-Pad10)") (class "Default")
      (node (ref "J4") (pin "10") (pinfunction "10_10") (pintype "passive"))
    )
    (net (code "148") (name "unconnected-(J4-Pad11)") (class "Default")
      (node (ref "J4") (pin "11") (pinfunction "11_11") (pintype "passive"))
    )
    (net (code "149") (name "unconnected-(J4-Pad13)") (class "Default")
      (node (ref "J4") (pin "13") (pinfunction "13_13") (pintype "passive"))
    )
    (net (code "150") (name "unconnected-(J4-Pad15)") (class "Default")
      (node (ref "J4") (pin "15") (pinfunction "15_15") (pintype "passive"))
    )
    (net (code "151") (name "unconnected-(J4-Pad16)") (class "Default")
      (node (ref "J4") (pin "16") (pinfunction "16_16") (pintype "passive"))
    )
    (net (code "152") (name "unconnected-(J4-Pad17)") (class "Default")
      (node (ref "J4") (pin "17") (pinfunction "17_17") (pintype "passive"))
    )
    (net (code "153") (name "unconnected-(J4-Pad18)") (class "Default")
      (node (ref "J4") (pin "18") (pinfunction "18_18") (pintype "passive"))
    )
    (net (code "154") (name "unconnected-(J4-Pad19)") (class "Default")
      (node (ref "J4") (pin "19") (pinfunction "19_19") (pintype "passive"))
    )
    (net (code "155") (name "unconnected-(J4-Pad20)") (class "Default")
      (node (ref "J4") (pin "20") (pinfunction "20_20") (pintype "passive"))
    )
    (net (code "156") (name "unconnected-(PS1-VADJ-Pad12)") (class "Default")
      (node (ref "PS1") (pin "12") (pinfunction "VADJ_12") (pintype "passive"))
    )
    (net (code "157") (name "unconnected-(PS2-VADJ-Pad12)") (class "Default")
      (node (ref "PS2") (pin "12") (pinfunction "VADJ_12") (pintype "passive"))
    )
  )
)
